# Sheet1.net
KiCad netlist of a schematic drawn in Altium Designer
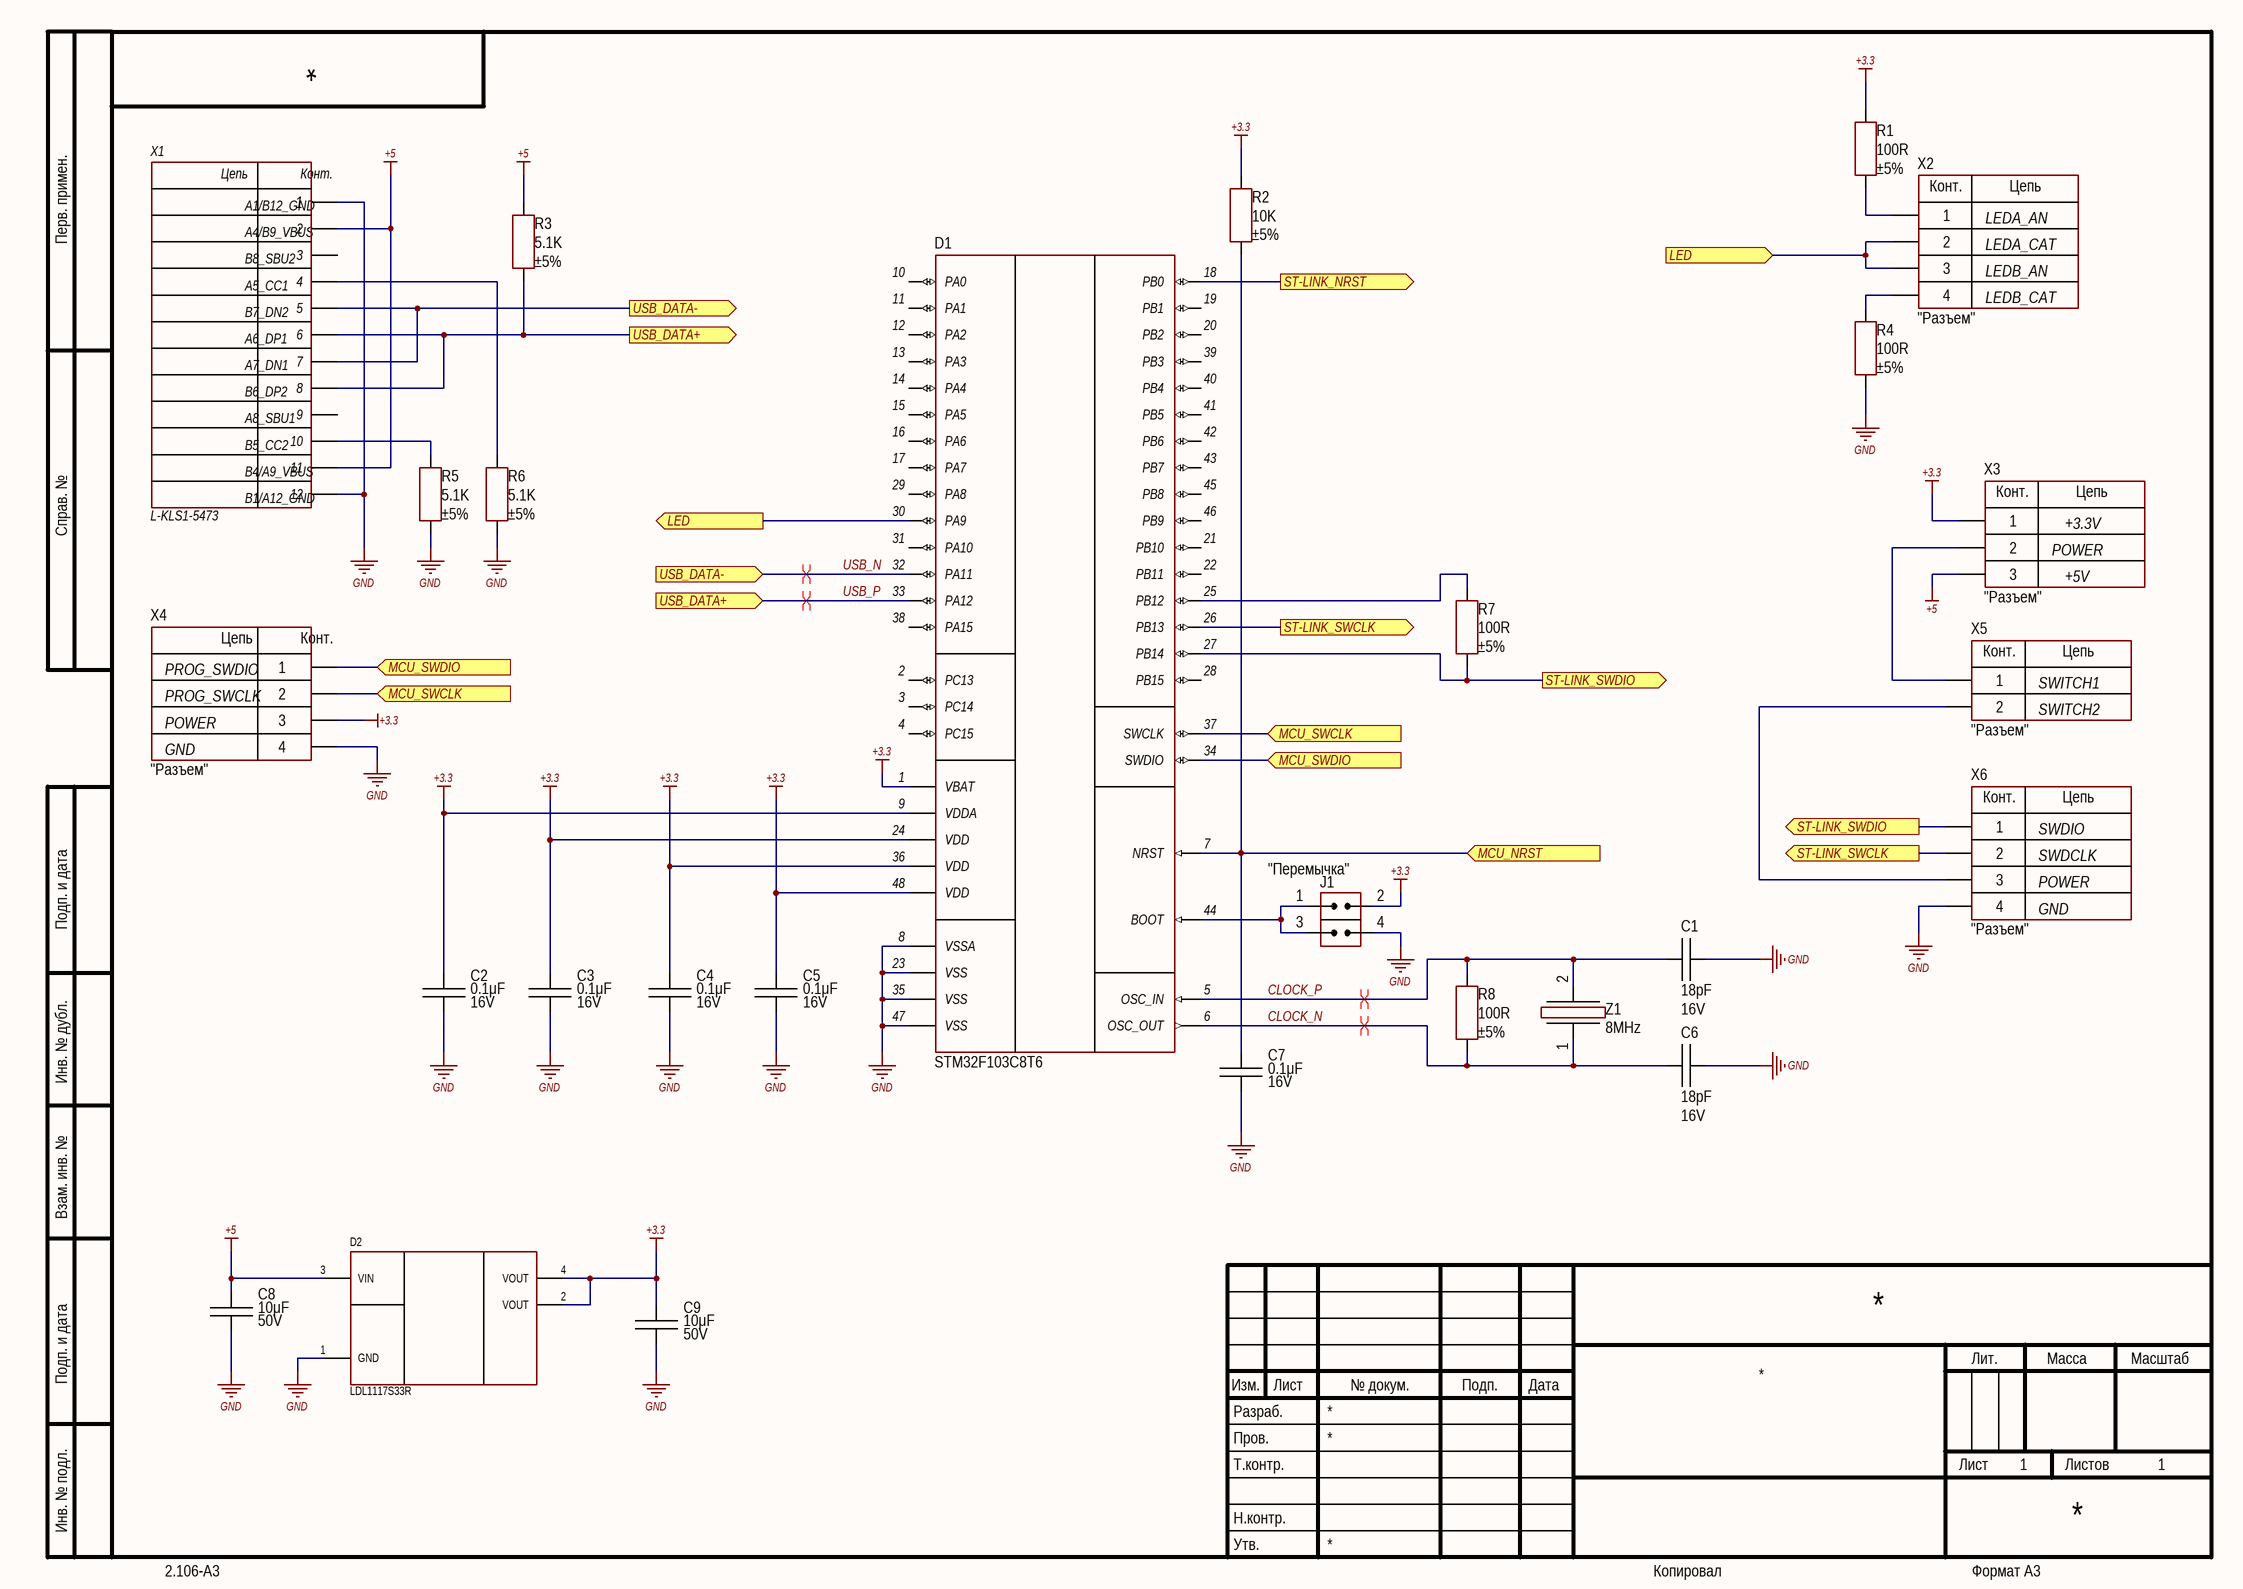
[diagram p0: Sheet1.SchDoc]

(export (version "E")
  (design (tool "Eeschema 10.0.6"))
  (components
    (comp (ref "C1")
      (value "18pF")
      (footprint "CAP: 0603")
      (fields
        (field (name "MANUFACTURER") "Yageo")
        (field (name "PARTNUMBER") "CC0603KRX7R7BB104")
        (field (name "VALUEMANUFACTURERPARTNUMBER") "Ceramic capacitor, 18pF, X7R, ±10%, 16V, 0603, -55...+125°C")
        (field (name "VOLTAGE") "16V")
      )
      (libsource (lib "capacitor") (part "Ceramic_0603"))
    )
    (comp (ref "C2")
      (value "0.1μF")
      (footprint "CAP: 0603")
      (fields
        (field (name "MANUFACTURER") "Yageo")
        (field (name "PARTNUMBER") "CC0603KRX7R7BB104")
        (field (name "VALUEMANUFACTURERPARTNUMBER") "Ceramic capacitor, 0.1μF, X7R, ±10%, 16V, 0603, -55...+125°C")
        (field (name "VOLTAGE") "16V")
      )
      (libsource (lib "capacitor") (part "Ceramic_0603"))
    )
    (comp (ref "C3")
      (value "0.1μF")
      (footprint "CAP: 0603")
      (fields
        (field (name "MANUFACTURER") "Yageo")
        (field (name "PARTNUMBER") "CC0603KRX7R7BB104")
        (field (name "VALUEMANUFACTURERPARTNUMBER") "Ceramic capacitor, 0.1μF, X7R, ±10%, 16V, 0603, -55...+125°C")
        (field (name "VOLTAGE") "16V")
      )
      (libsource (lib "capacitor") (part "Ceramic_0603"))
    )
    (comp (ref "C4")
      (value "0.1μF")
      (footprint "CAP: 0603")
      (fields
        (field (name "MANUFACTURER") "Yageo")
        (field (name "PARTNUMBER") "CC0603KRX7R7BB104")
        (field (name "VALUEMANUFACTURERPARTNUMBER") "Ceramic capacitor, 0.1μF, X7R, ±10%, 16V, 0603, -55...+125°C")
        (field (name "VOLTAGE") "16V")
      )
      (libsource (lib "capacitor") (part "Ceramic_0603"))
    )
    (comp (ref "C5")
      (value "0.1μF")
      (footprint "CAP: 0603")
      (fields
        (field (name "MANUFACTURER") "Yageo")
        (field (name "PARTNUMBER") "CC0603KRX7R7BB104")
        (field (name "VALUEMANUFACTURERPARTNUMBER") "Ceramic capacitor, 0.1μF, X7R, ±10%, 16V, 0603, -55...+125°C")
        (field (name "VOLTAGE") "16V")
      )
      (libsource (lib "capacitor") (part "Ceramic_0603"))
    )
    (comp (ref "C6")
      (value "18pF")
      (footprint "CAP: 0603")
      (fields
        (field (name "MANUFACTURER") "Yageo")
        (field (name "PARTNUMBER") "CC0603KRX7R7BB104")
        (field (name "VALUEMANUFACTURERPARTNUMBER") "Ceramic capacitor, 18pF, X7R, ±10%, 16V, 0603, -55...+125°C")
        (field (name "VOLTAGE") "16V")
      )
      (libsource (lib "capacitor") (part "Ceramic_0603"))
    )
    (comp (ref "C7")
      (value "0.1μF")
      (footprint "CAP: 0603")
      (fields
        (field (name "MANUFACTURER") "Yageo")
        (field (name "PARTNUMBER") "CC0603KRX7R7BB104")
        (field (name "VALUEMANUFACTURERPARTNUMBER") "Ceramic capacitor, 0.1μF, X7R, ±10%, 16V, 0603, -55...+125°C")
        (field (name "VOLTAGE") "16V")
      )
      (libsource (lib "capacitor") (part "Ceramic_0603"))
    )
    (comp (ref "C8")
      (value "10μF")
      (footprint "CAP: 1206")
      (fields
        (field (name "MANUFACTURER") "Yageo")
        (field (name "PARTNUMBER") "CC1206KRX7R9BB104")
        (field (name "VALUEMANUFACTURERPARTNUMBER") "Ceramic capacitor, 10μF, X7R, ±10%, 50V, 1206, -55...+125°C")
        (field (name "VOLTAGE") "50V")
      )
      (libsource (lib "capacitor") (part "Ceramic_1206"))
    )
    (comp (ref "C9")
      (value "10μF")
      (footprint "CAP: 1206")
      (fields
        (field (name "MANUFACTURER") "Yageo")
        (field (name "PARTNUMBER") "CC1206KRX7R9BB104")
        (field (name "VALUEMANUFACTURERPARTNUMBER") "Ceramic capacitor, 10μF, X7R, ±10%, 50V, 1206, -55...+125°C")
        (field (name "VOLTAGE") "50V")
      )
      (libsource (lib "capacitor") (part "Ceramic_1206"))
    )
    (comp (ref "D1")
      (value "~")
      (footprint "48-LQFP")
      (description "Cortex-M3")
      (fields
        (field (name "MANUFACTURER") "STMicroelectronics")
        (field (name "VALUEMANUFACTURERPARTNUMBER") "IC microcontroller, 32-Bit, Cortex-M3, 72MHz, 64KB, 20KB, 2...3.6V, -40...+85°C, 48-LQFP")
        (field (name "PARTNUMBER") "STM32F103C8T6")
      )
      (libsource (lib "ic-mcu") (part "STM32F103C8T6"))
    )
    (comp (ref "D2")
      (value "~")
      (footprint "SOT223")
      (description "Linear voltage regulator")
      (fields
        (field (name "MANUFACTURER") "STMicroelectronics")
        (field (name "VALUEMANUFACTURERPARTNUMBER") "Linear voltage regulator, input 3.9...18V, 0.6V, output 3.3V, 1.2A, -40...+85°C, SOT223")
        (field (name "PARTNUMBER") "LDL1117S33R")
      )
      (libsource (lib "ic-power-supply") (part "LDL1117S33R"))
    )
    (comp (ref "J1")
      (value "~")
      (footprint "CON: JUMPER x2")
      (fields (field (name "COMMENTTEXT") "\"Перемычка\""))
      (libsource (lib "connector") (part "Jumper_double"))
    )
    (comp (ref "R1")
      (value "100R")
      (footprint "RES: 0603")
      (fields
        (field (name "MANUFACTURER") "Yageo")
        (field (name "PARTNUMBER") "RC0603JR-07100RL")
        (field (name "VALUEMANUFACTURERPARTNUMBER") "Resistor film, 100R, ±5%, 0603, 0.1W, -55...+125°C")
        (field (name "TOLERANCE") "±5%")
      )
      (libsource (lib "resistor") (part "Resistor_0603"))
    )
    (comp (ref "R2")
      (value "10K")
      (footprint "RES: 0603")
      (fields
        (field (name "MANUFACTURER") "Yageo")
        (field (name "PARTNUMBER") "RC0603JR-07100RL")
        (field (name "VALUEMANUFACTURERPARTNUMBER") "Resistor film, 10K, ±5%, 0603, 0.1W, -55...+125°C")
        (field (name "TOLERANCE") "±5%")
      )
      (libsource (lib "resistor") (part "Resistor_0603"))
    )
    (comp (ref "R3")
      (value "5.1K")
      (footprint "RES: 0603")
      (fields
        (field (name "MANUFACTURER") "Yageo")
        (field (name "PARTNUMBER") "RC0603JR-07100RL")
        (field (name "VALUEMANUFACTURERPARTNUMBER") "Resistor film, 5.1K, ±5%, 0603, 0.1W, -55...+125°C")
        (field (name "TOLERANCE") "±5%")
      )
      (libsource (lib "resistor") (part "Resistor_0603"))
    )
    (comp (ref "R4")
      (value "100R")
      (footprint "RES: 0603")
      (fields
        (field (name "MANUFACTURER") "Yageo")
        (field (name "PARTNUMBER") "RC0603JR-07100RL")
        (field (name "VALUEMANUFACTURERPARTNUMBER") "Resistor film, 100R, ±5%, 0603, 0.1W, -55...+125°C")
        (field (name "TOLERANCE") "±5%")
      )
      (libsource (lib "resistor") (part "Resistor_0603"))
    )
    (comp (ref "R5")
      (value "5.1K")
      (footprint "RES: 0603")
      (fields
        (field (name "MANUFACTURER") "Yageo")
        (field (name "PARTNUMBER") "RC0603JR-07100RL")
        (field (name "VALUEMANUFACTURERPARTNUMBER") "Resistor film, 5.1K, ±5%, 0603, 0.1W, -55...+125°C")
        (field (name "TOLERANCE") "±5%")
      )
      (libsource (lib "resistor") (part "Resistor_0603"))
    )
    (comp (ref "R6")
      (value "5.1K")
      (footprint "RES: 0603")
      (fields
        (field (name "MANUFACTURER") "Yageo")
        (field (name "PARTNUMBER") "RC0603JR-07100RL")
        (field (name "VALUEMANUFACTURERPARTNUMBER") "Resistor film, 5.1K, ±5%, 0603, 0.1W, -55...+125°C")
        (field (name "TOLERANCE") "±5%")
      )
      (libsource (lib "resistor") (part "Resistor_0603"))
    )
    (comp (ref "R7")
      (value "100R")
      (footprint "RES: 0603")
      (fields
        (field (name "MANUFACTURER") "Yageo")
        (field (name "PARTNUMBER") "RC0603JR-07100RL")
        (field (name "VALUEMANUFACTURERPARTNUMBER") "Resistor film, 100R, ±5%, 0603, 0.1W, -55...+125°C")
        (field (name "TOLERANCE") "±5%")
      )
      (libsource (lib "resistor") (part "Resistor_0603"))
    )
    (comp (ref "R8")
      (value "100R")
      (footprint "RES: 0603")
      (fields
        (field (name "MANUFACTURER") "Yageo")
        (field (name "PARTNUMBER") "RC0603JR-07100RL")
        (field (name "VALUEMANUFACTURERPARTNUMBER") "Resistor film, 100R, ±5%, 0603, 0.1W, -55...+125°C")
        (field (name "TOLERANCE") "±5%")
      )
      (libsource (lib "resistor") (part "Resistor_0603"))
    )
    (comp (ref "X1")
      (value "~")
      (footprint "USB type-C")
      (description "Разъем L-KLS1-5473 / гнездо USB C 3.1 на плату (C8)")
      (fields
        (field (name "MANUFACTURER") "KLS")
        (field (name "PARTNUMBER") "L-KLS1-5473")
        (field (name "COMMENTTEXT") "L-KLS1-5473")
      )
      (libsource (lib "connector") (part "L-KLS1-5473"))
    )
    (comp (ref "X2")
      (value "~")
      (footprint "CON: PBS-4")
      (fields
        (field (name "MANUFACTURER") "Connfly")
        (field (name "VALUEMANUFACTURERPARTNUMBER") "Connector, 4pin, 2.54mm, 500VAC, 3A")
        (field (name "PARTNUMBER") "PBS-4")
        (field (name "COMMENTTEXT") "\"Разъем\"")
      )
      (libsource (lib "connector") (part "PBS-4"))
    )
    (comp (ref "X3")
      (value "~")
      (footprint "CON: PLS-3")
      (fields
        (field (name "MANUFACTURER") "Connfly")
        (field (name "VALUEMANUFACTURERPARTNUMBER") "Connector, 3pin, 2.54mm, 500VAC, 3A")
        (field (name "PARTNUMBER") "PLS-3")
        (field (name "COMMENTTEXT") "\"Разъем\"")
      )
      (libsource (lib "connector") (part "PLS-3"))
    )
    (comp (ref "X4")
      (value "~")
      (footprint "CON: PLS-4")
      (fields
        (field (name "MANUFACTURER") "Connfly")
        (field (name "VALUEMANUFACTURERPARTNUMBER") "Connector, 4pin, 2.54mm, 500VAC, 3A")
        (field (name "PARTNUMBER") "PLS-4")
        (field (name "COMMENTTEXT") "\"Разъем\"")
      )
      (libsource (lib "connector") (part "PLS-4"))
    )
    (comp (ref "X5")
      (value "~")
      (footprint "CON: PLS-2")
      (fields
        (field (name "MANUFACTURER") "Connfly")
        (field (name "VALUEMANUFACTURERPARTNUMBER") "Connector, 2pin, 2.54mm, 500VAC, 3A")
        (field (name "PARTNUMBER") "PLS-2")
        (field (name "COMMENTTEXT") "\"Разъем\"")
      )
      (libsource (lib "connector") (part "PLS-2"))
    )
    (comp (ref "X6")
      (value "~")
      (footprint "CON: PBS-4")
      (fields
        (field (name "MANUFACTURER") "Connfly")
        (field (name "VALUEMANUFACTURERPARTNUMBER") "Connector, 4pin, 2.54mm, 500VAC, 3A")
        (field (name "PARTNUMBER") "PBS-4")
        (field (name "COMMENTTEXT") "\"Разъем\"")
      )
      (libsource (lib "connector") (part "PBS-4"))
    )
    (comp (ref "Z1")
      (value "~")
      (footprint "OSC: HC-49S")
      (fields
        (field (name "MANUFACTURER") "Epson")
        (field (name "PARTNUMBER") "FC-135 32.7680KA-A5")
        (field (name "VALUEMANUFACTURERPARTNUMBER") "Crystal, 8MHz, 12.5pF, ±20ppm, case 3215, -40...+85°C")
        (field (name "FREQUENCY") "8MHz")
      )
      (libsource (lib "oscilator") (part "Crystal_HC-49"))
    )
  )
  (nets
    (net (code "1") (name "+3.3") (class "Default")
      (node (ref "C2") (pin "2") (pinfunction "2_2") (pintype "passive"))
      (node (ref "C3") (pin "2") (pinfunction "2_2") (pintype "passive"))
      (node (ref "C4") (pin "2") (pinfunction "2_2") (pintype "passive"))
      (node (ref "C5") (pin "2") (pinfunction "2_2") (pintype "passive"))
      (node (ref "C9") (pin "2") (pinfunction "2_2") (pintype "passive"))
      (node (ref "D1") (pin "1") (pinfunction "VBAT_1") (pintype "power_in"))
      (node (ref "D1") (pin "24") (pinfunction "VDD_24") (pintype "power_in"))
      (node (ref "D1") (pin "36") (pinfunction "VDD_36") (pintype "power_in"))
      (node (ref "D1") (pin "48") (pinfunction "VDD_48") (pintype "power_in"))
      (node (ref "D1") (pin "9") (pinfunction "VDDA_9") (pintype "power_in"))
      (node (ref "D2") (pin "2") (pinfunction "VOUT_2") (pintype "power_in"))
      (node (ref "D2") (pin "4") (pinfunction "VOUT_4") (pintype "power_in"))
      (node (ref "J1") (pin "2") (pinfunction "IN_2") (pintype "passive"))
      (node (ref "R1") (pin "2") (pinfunction "2_2") (pintype "passive"))
      (node (ref "R2") (pin "2") (pinfunction "2_2") (pintype "passive"))
      (node (ref "X3") (pin "1") (pinfunction "1_1") (pintype "passive"))
      (node (ref "X4") (pin "3") (pinfunction "3_3") (pintype "power_in"))
    )
    (net (code "2") (name "+5") (class "Default")
      (node (ref "C8") (pin "2") (pinfunction "2_2") (pintype "passive"))
      (node (ref "D2") (pin "3") (pinfunction "VIN_3") (pintype "power_in"))
      (node (ref "R3") (pin "2") (pinfunction "2_2") (pintype "passive"))
      (node (ref "X1") (pin "11") (pinfunction "11_11") (pintype "passive"))
      (node (ref "X1") (pin "2") (pinfunction "2_2") (pintype "passive"))
      (node (ref "X3") (pin "3") (pinfunction "3_3") (pintype "power_in"))
    )
    (net (code "3") (name "/CLOCK_N") (class "Default")
      (node (ref "C6") (pin "2") (pinfunction "2_2") (pintype "passive"))
      (node (ref "D1") (pin "6") (pinfunction "OSC_OUT_6") (pintype "output"))
      (node (ref "R8") (pin "1") (pinfunction "1_1") (pintype "passive"))
      (node (ref "Z1") (pin "1") (pinfunction "1_1") (pintype "passive"))
    )
    (net (code "4") (name "/CLOCK_P") (class "Default")
      (node (ref "C1") (pin "2") (pinfunction "2_2") (pintype "passive"))
      (node (ref "D1") (pin "5") (pinfunction "OSC_IN_5") (pintype "input"))
      (node (ref "R8") (pin "2") (pinfunction "2_2") (pintype "passive"))
      (node (ref "Z1") (pin "2") (pinfunction "2_2") (pintype "passive"))
    )
    (net (code "5") (name "/LED") (class "Default")
      (node (ref "D1") (pin "30") (pinfunction "PA9_30") (pintype "bidirectional"))
      (node (ref "X2") (pin "2") (pinfunction "2_2") (pintype "passive"))
      (node (ref "X2") (pin "3") (pinfunction "3_3") (pintype "power_in"))
    )
    (net (code "6") (name "/MCU_NRST") (class "Default")
      (node (ref "C7") (pin "2") (pinfunction "2_2") (pintype "passive"))
      (node (ref "D1") (pin "7") (pinfunction "NRST_7") (pintype "input"))
      (node (ref "R2") (pin "1") (pinfunction "1_1") (pintype "passive"))
    )
    (net (code "7") (name "/MCU_SWCLK") (class "Default")
      (node (ref "D1") (pin "37") (pinfunction "SWCLK_37") (pintype "bidirectional"))
      (node (ref "X4") (pin "2") (pinfunction "2_2") (pintype "passive"))
    )
    (net (code "8") (name "/MCU_SWDIO") (class "Default")
      (node (ref "D1") (pin "34") (pinfunction "SWDIO_34") (pintype "bidirectional"))
      (node (ref "X4") (pin "1") (pinfunction "1_1") (pintype "passive"))
    )
    (net (code "9") (name "/ST-LINK_NRST") (class "Default")
      (node (ref "D1") (pin "18") (pinfunction "PB0_18") (pintype "bidirectional"))
    )
    (net (code "10") (name "/ST-LINK_SWCLK") (class "Default")
      (node (ref "D1") (pin "26") (pinfunction "PB13_26") (pintype "bidirectional"))
      (node (ref "X6") (pin "2") (pinfunction "2_2") (pintype "passive"))
    )
    (net (code "11") (name "/ST-LINK_SWDIO") (class "Default")
      (node (ref "D1") (pin "27") (pinfunction "PB14_27") (pintype "bidirectional"))
      (node (ref "R7") (pin "1") (pinfunction "1_1") (pintype "passive"))
      (node (ref "X6") (pin "1") (pinfunction "1_1") (pintype "passive"))
    )
    (net (code "12") (name "/USB_N") (class "Default")
      (node (ref "D1") (pin "32") (pinfunction "PA11_32") (pintype "bidirectional"))
      (node (ref "X1") (pin "5") (pinfunction "5_5") (pintype "passive"))
      (node (ref "X1") (pin "7") (pinfunction "7_7") (pintype "passive"))
    )
    (net (code "13") (name "/USB_P") (class "Default")
      (node (ref "D1") (pin "33") (pinfunction "PA12_33") (pintype "bidirectional"))
      (node (ref "R3") (pin "1") (pinfunction "1_1") (pintype "passive"))
      (node (ref "X1") (pin "6") (pinfunction "6_6") (pintype "passive"))
      (node (ref "X1") (pin "8") (pinfunction "8_8") (pintype "passive"))
    )
    (net (code "14") (name "GND") (class "Default")
      (node (ref "C1") (pin "1") (pinfunction "1_1") (pintype "passive"))
      (node (ref "C2") (pin "1") (pinfunction "1_1") (pintype "passive"))
      (node (ref "C3") (pin "1") (pinfunction "1_1") (pintype "passive"))
      (node (ref "C4") (pin "1") (pinfunction "1_1") (pintype "passive"))
      (node (ref "C5") (pin "1") (pinfunction "1_1") (pintype "passive"))
      (node (ref "C6") (pin "1") (pinfunction "1_1") (pintype "passive"))
      (node (ref "C7") (pin "1") (pinfunction "1_1") (pintype "passive"))
      (node (ref "C8") (pin "1") (pinfunction "1_1") (pintype "passive"))
      (node (ref "C9") (pin "1") (pinfunction "1_1") (pintype "passive"))
      (node (ref "D1") (pin "23") (pinfunction "VSS_23") (pintype "power_in"))
      (node (ref "D1") (pin "35") (pinfunction "VSS_35") (pintype "power_in"))
      (node (ref "D1") (pin "47") (pinfunction "VSS_47") (pintype "power_in"))
      (node (ref "D1") (pin "8") (pinfunction "VSSA_8") (pintype "power_in"))
      (node (ref "D2") (pin "1") (pinfunction "GND_1") (pintype "power_in"))
      (node (ref "J1") (pin "4") (pinfunction "IN_4") (pintype "passive"))
      (node (ref "R4") (pin "1") (pinfunction "1_1") (pintype "passive"))
      (node (ref "R5") (pin "1") (pinfunction "1_1") (pintype "passive"))
      (node (ref "R6") (pin "1") (pinfunction "1_1") (pintype "passive"))
      (node (ref "X1") (pin "1") (pinfunction "1_1") (pintype "passive"))
      (node (ref "X1") (pin "12") (pinfunction "12_12") (pintype "passive"))
      (node (ref "X4") (pin "4") (pinfunction "4_4") (pintype "power_in"))
      (node (ref "X6") (pin "4") (pinfunction "4_4") (pintype "power_in"))
    )
    (net (code "15") (name "Net-(D1-BOOT)") (class "Default")
      (node (ref "D1") (pin "44") (pinfunction "BOOT_44") (pintype "input"))
      (node (ref "J1") (pin "1") (pinfunction "IN_1") (pintype "passive"))
      (node (ref "J1") (pin "3") (pinfunction "IN_3") (pintype "passive"))
    )
    (net (code "16") (name "Net-(D1-PB12)") (class "Default")
      (node (ref "D1") (pin "25") (pinfunction "PB12_25") (pintype "bidirectional"))
      (node (ref "R7") (pin "2") (pinfunction "2_2") (pintype "passive"))
    )
    (net (code "17") (name "Net-(R1-Pad1)") (class "Default")
      (node (ref "R1") (pin "1") (pinfunction "1_1") (pintype "passive"))
      (node (ref "X2") (pin "1") (pinfunction "1_1") (pintype "passive"))
    )
    (net (code "18") (name "Net-(R4-Pad2)") (class "Default")
      (node (ref "R4") (pin "2") (pinfunction "2_2") (pintype "passive"))
      (node (ref "X2") (pin "4") (pinfunction "4_4") (pintype "power_in"))
    )
    (net (code "19") (name "Net-(R5-Pad2)") (class "Default")
      (node (ref "R5") (pin "2") (pinfunction "2_2") (pintype "passive"))
      (node (ref "X1") (pin "10") (pinfunction "10_10") (pintype "passive"))
    )
    (net (code "20") (name "Net-(R6-Pad2)") (class "Default")
      (node (ref "R6") (pin "2") (pinfunction "2_2") (pintype "passive"))
      (node (ref "X1") (pin "4") (pinfunction "4_4") (pintype "passive"))
    )
    (net (code "21") (name "Net-(X3-Pad2)") (class "Default")
      (node (ref "X3") (pin "2") (pinfunction "2_2") (pintype "passive"))
      (node (ref "X5") (pin "1") (pinfunction "1_1") (pintype "passive"))
    )
    (net (code "22") (name "Net-(X5-Pad2)") (class "Default")
      (node (ref "X5") (pin "2") (pinfunction "2_2") (pintype "passive"))
      (node (ref "X6") (pin "3") (pinfunction "3_3") (pintype "power_in"))
    )
    (net (code "23") (name "unconnected-(D1-PA0-Pad10)") (class "Default")
      (node (ref "D1") (pin "10") (pinfunction "PA0_10") (pintype "bidirectional"))
    )
    (net (code "24") (name "unconnected-(D1-PA1-Pad11)") (class "Default")
      (node (ref "D1") (pin "11") (pinfunction "PA1_11") (pintype "bidirectional"))
    )
    (net (code "25") (name "unconnected-(D1-PA2-Pad12)") (class "Default")
      (node (ref "D1") (pin "12") (pinfunction "PA2_12") (pintype "bidirectional"))
    )
    (net (code "26") (name "unconnected-(D1-PA3-Pad13)") (class "Default")
      (node (ref "D1") (pin "13") (pinfunction "PA3_13") (pintype "bidirectional"))
    )
    (net (code "27") (name "unconnected-(D1-PA4-Pad14)") (class "Default")
      (node (ref "D1") (pin "14") (pinfunction "PA4_14") (pintype "bidirectional"))
    )
    (net (code "28") (name "unconnected-(D1-PA5-Pad15)") (class "Default")
      (node (ref "D1") (pin "15") (pinfunction "PA5_15") (pintype "bidirectional"))
    )
    (net (code "29") (name "unconnected-(D1-PA6-Pad16)") (class "Default")
      (node (ref "D1") (pin "16") (pinfunction "PA6_16") (pintype "bidirectional"))
    )
    (net (code "30") (name "unconnected-(D1-PA7-Pad17)") (class "Default")
      (node (ref "D1") (pin "17") (pinfunction "PA7_17") (pintype "bidirectional"))
    )
    (net (code "31") (name "unconnected-(D1-PA8-Pad29)") (class "Default")
      (node (ref "D1") (pin "29") (pinfunction "PA8_29") (pintype "bidirectional"))
    )
    (net (code "32") (name "unconnected-(D1-PA10-Pad31)") (class "Default")
      (node (ref "D1") (pin "31") (pinfunction "PA10_31") (pintype "bidirectional"))
    )
    (net (code "33") (name "unconnected-(D1-PA15-Pad38)") (class "Default")
      (node (ref "D1") (pin "38") (pinfunction "PA15_38") (pintype "bidirectional"))
    )
    (net (code "34") (name "unconnected-(D1-PB1-Pad19)") (class "Default")
      (node (ref "D1") (pin "19") (pinfunction "PB1_19") (pintype "bidirectional"))
    )
    (net (code "35") (name "unconnected-(D1-PB2-Pad20)") (class "Default")
      (node (ref "D1") (pin "20") (pinfunction "PB2_20") (pintype "bidirectional"))
    )
    (net (code "36") (name "unconnected-(D1-PB3-Pad39)") (class "Default")
      (node (ref "D1") (pin "39") (pinfunction "PB3_39") (pintype "bidirectional"))
    )
    (net (code "37") (name "unconnected-(D1-PB4-Pad40)") (class "Default")
      (node (ref "D1") (pin "40") (pinfunction "PB4_40") (pintype "bidirectional"))
    )
    (net (code "38") (name "unconnected-(D1-PB5-Pad41)") (class "Default")
      (node (ref "D1") (pin "41") (pinfunction "PB5_41") (pintype "bidirectional"))
    )
    (net (code "39") (name "unconnected-(D1-PB6-Pad42)") (class "Default")
      (node (ref "D1") (pin "42") (pinfunction "PB6_42") (pintype "bidirectional"))
    )
    (net (code "40") (name "unconnected-(D1-PB7-Pad43)") (class "Default")
      (node (ref "D1") (pin "43") (pinfunction "PB7_43") (pintype "bidirectional"))
    )
    (net (code "41") (name "unconnected-(D1-PB8-Pad45)") (class "Default")
      (node (ref "D1") (pin "45") (pinfunction "PB8_45") (pintype "bidirectional"))
    )
    (net (code "42") (name "unconnected-(D1-PB9-Pad46)") (class "Default")
      (node (ref "D1") (pin "46") (pinfunction "PB9_46") (pintype "bidirectional"))
    )
    (net (code "43") (name "unconnected-(D1-PB10-Pad21)") (class "Default")
      (node (ref "D1") (pin "21") (pinfunction "PB10_21") (pintype "bidirectional"))
    )
    (net (code "44") (name "unconnected-(D1-PB11-Pad22)") (class "Default")
      (node (ref "D1") (pin "22") (pinfunction "PB11_22") (pintype "bidirectional"))
    )
    (net (code "45") (name "unconnected-(D1-PB15-Pad28)") (class "Default")
      (node (ref "D1") (pin "28") (pinfunction "PB15_28") (pintype "bidirectional"))
    )
    (net (code "46") (name "unconnected-(D1-PC13-Pad2)") (class "Default")
      (node (ref "D1") (pin "2") (pinfunction "PC13_2") (pintype "bidirectional"))
    )
    (net (code "47") (name "unconnected-(D1-PC14-Pad3)") (class "Default")
      (node (ref "D1") (pin "3") (pinfunction "PC14_3") (pintype "bidirectional"))
    )
    (net (code "48") (name "unconnected-(D1-PC15-Pad4)") (class "Default")
      (node (ref "D1") (pin "4") (pinfunction "PC15_4") (pintype "bidirectional"))
    )
    (net (code "49") (name "unconnected-(X1-Pad3)") (class "Default")
      (node (ref "X1") (pin "3") (pinfunction "3_3") (pintype "passive"))
    )
    (net (code "50") (name "unconnected-(X1-Pad9)") (class "Default")
      (node (ref "X1") (pin "9") (pinfunction "9_9") (pintype "passive"))
    )
  )
)
